# Cerebro_4_7.net
KiCad netlist of a schematic drawn in EAGLE
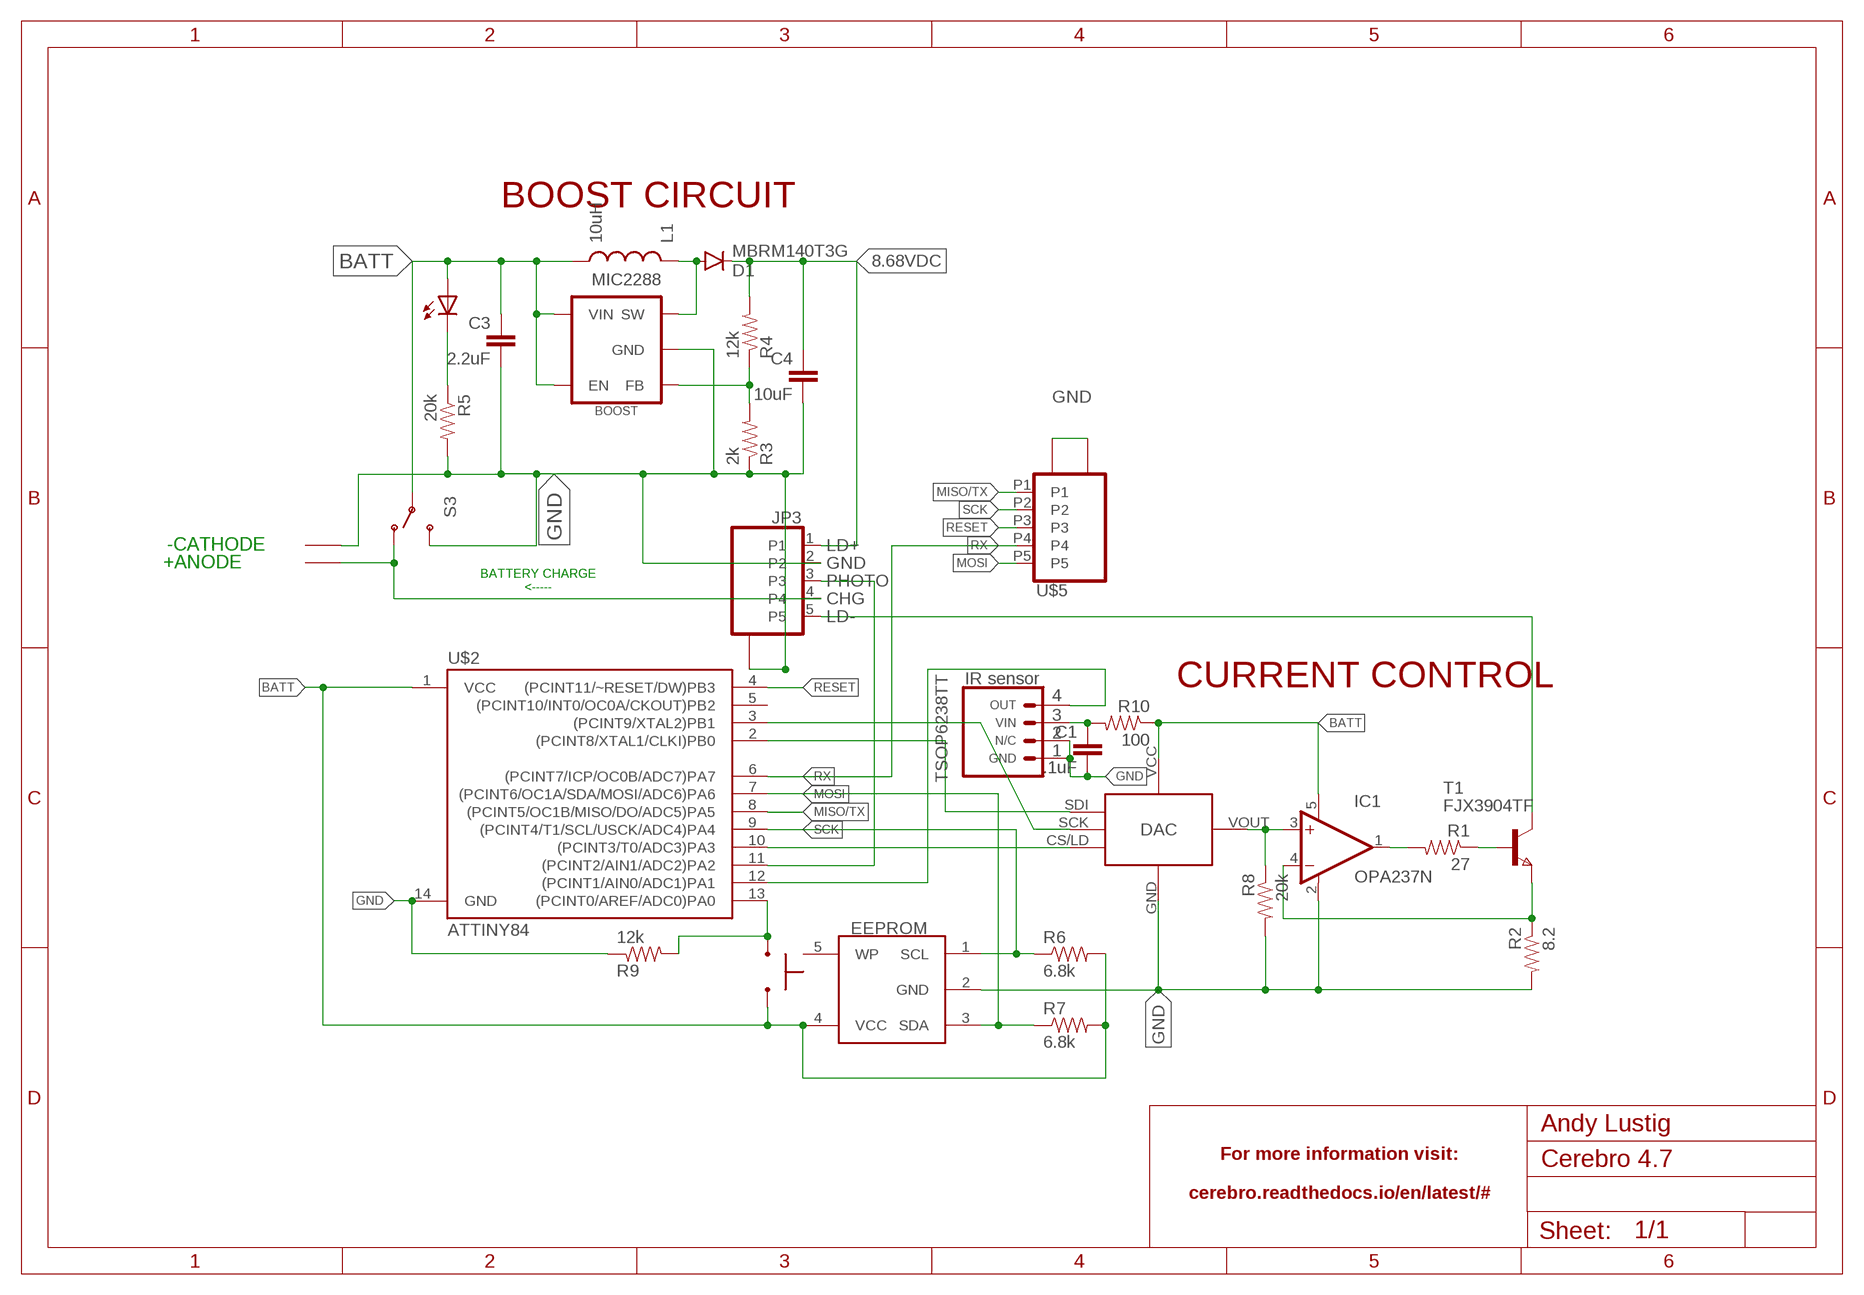
[diagram p0: schematic, sheet 1]

(export (version "E")
  (design (tool "Eeschema 10.0.6"))
  (components
    (comp (ref "C1")
      (value ".1uF")
      (footprint "eagle-import:0603-CAP")
      (libsource (lib "eagle-import") (part "CAP0603-CAP"))
    )
    (comp (ref "C3")
      (value "2.2uF")
      (footprint "eagle-import:0805")
      (libsource (lib "eagle-import") (part "CAP0805"))
    )
    (comp (ref "C4")
      (value "10uF")
      (footprint "eagle-import:0805")
      (libsource (lib "eagle-import") (part "CAP0805"))
    )
    (comp (ref "D1")
      (value "MBRM140T3G")
      (footprint "eagle-import:POWERMITE")
      (libsource (lib "eagle-import") (part "DIODEPOWERMITE"))
    )
    (comp (ref "IC1")
      (value "OPA237N")
      (footprint "eagle-import:SOT23-5")
      (fields (field (name "MF") "TEXAS INSTRUMENTS") (field (name "MPN") "OPA237NA/250"))
      (libsource (lib "eagle-import") (part "OPA237N"))
    )
    (comp (ref "INDICATOR_LED")
      (value "LED")
      (footprint "eagle-import:CHIP-LED0603")
      (libsource (lib "eagle-import") (part "LEDCHIP-LED0603"))
    )
    (comp (ref "JP3")
      (value "USB_MICROB_PLUG-PTH2")
      (footprint "eagle-import:MICRO-B-TH")
      (libsource (lib "eagle-import") (part "USB_MICROB_PLUG-PTH2"))
    )
    (comp (ref "L1")
      (value "10uH")
      (footprint "eagle-import:1812")
      (libsource (lib "eagle-import") (part "INDUCTORLQH4"))
    )
    (comp (ref "MIC2288")
      (value "BOOST")
      (footprint "eagle-import:SOT23-5")
      (libsource (lib "eagle-import") (part "BOOST_CONVERTER"))
    )
    (comp (ref "R1")
      (value "27")
      (footprint "eagle-import:0805")
      (libsource (lib "eagle-import") (part "RESISTOR0805-RES"))
    )
    (comp (ref "R2")
      (value "8.2")
      (footprint "eagle-import:0805")
      (libsource (lib "eagle-import") (part "RESISTOR0805-RES"))
    )
    (comp (ref "R3")
      (value "2k")
      (footprint "eagle-import:0805")
      (libsource (lib "eagle-import") (part "RESISTOR0805-RES"))
    )
    (comp (ref "R4")
      (value "12k")
      (footprint "eagle-import:0805")
      (libsource (lib "eagle-import") (part "RESISTOR0805-RES"))
    )
    (comp (ref "R5")
      (value "20k")
      (footprint "eagle-import:0603-RES")
      (libsource (lib "eagle-import") (part "RESISTOR0603-RES"))
    )
    (comp (ref "R6")
      (value "6.8k")
      (footprint "eagle-import:0805")
      (libsource (lib "eagle-import") (part "RESISTOR0805-RES"))
    )
    (comp (ref "R7")
      (value "6.8k")
      (footprint "eagle-import:0805")
      (libsource (lib "eagle-import") (part "RESISTOR0805-RES"))
    )
    (comp (ref "R8")
      (value "20k")
      (footprint "eagle-import:0805")
      (libsource (lib "eagle-import") (part "RESISTOR0805-RES"))
    )
    (comp (ref "R9")
      (value "12k")
      (footprint "eagle-import:0805")
      (libsource (lib "eagle-import") (part "RESISTOR0805-RES"))
    )
    (comp (ref "R10")
      (value "100")
      (footprint "eagle-import:0603-RES")
      (libsource (lib "eagle-import") (part "RESISTOR0603-RES"))
    )
    (comp (ref "S3")
      (value "SWITCH-SPDTSMD2")
      (footprint "eagle-import:SWITCH-SPDT-SMD")
      (libsource (lib "eagle-import") (part "SWITCH-SPDTSMD2"))
    )
    (comp (ref "SDF")
      (value "TSOP6238TT")
      (footprint "eagle-import:TSOP6")
      (libsource (lib "eagle-import") (part "TSOP6238TT"))
    )
    (comp (ref "T1")
      (value "FJX3904TF")
      (footprint "eagle-import:SOT323")
      (fields (field (name "MPN") "DSS4160U-7"))
      (libsource (lib "eagle-import") (part "NPNSOT323"))
    )
    (comp (ref "U$1")
      (value "DAC_LTC2630")
      (footprint "eagle-import:SC-70")
      (libsource (lib "eagle-import") (part "DAC_LTC2630"))
    )
    (comp (ref "U$2")
      (value "ATTINY84")
      (footprint "eagle-import:SO14")
      (libsource (lib "eagle-import") (part "ATTINY84"))
    )
    (comp (ref "U$3")
      (value "SWITCH-MOMENTARY-NO")
      (footprint "eagle-import:SWITCH_MOMENTARY_XS")
      (libsource (lib "eagle-import") (part "SWITCH-MOMENTARY-NO"))
    )
    (comp (ref "U$4")
      (value "EEPROM24C64A")
      (footprint "eagle-import:SOT23-5")
      (libsource (lib "eagle-import") (part "EEPROM24C64A"))
    )
    (comp (ref "U$5")
      (value "USB_SOCKET_MICRO_VERTHORIZONTAL")
      (footprint "eagle-import:USB_HORZ_MICRO_SMD")
      (libsource (lib "eagle-import") (part "USB_SOCKET_MICRO_VERTHORIZONTAL"))
    )
    (comp (ref "U$7")
      (value "BATT_TERMINAL")
      (footprint "eagle-import:BATT_TERMINAL")
      (libsource (lib "eagle-import") (part "BATT_TERMINAL"))
    )
    (comp (ref "U$8")
      (value "BATT_TERMINAL")
      (footprint "eagle-import:BATT_TERMINAL")
      (libsource (lib "eagle-import") (part "BATT_TERMINAL"))
    )
  )
  (nets
    (net (code "1") (name "8.68VDC") (class "Default")
      (node (ref "C4") (pin "1") (pinfunction "1_1") (pintype "passive"))
      (node (ref "D1") (pin "CATHODE") (pinfunction "C_CATHODE") (pintype "passive"))
      (node (ref "JP3") (pin "1") (pinfunction "P1_1") (pintype "bidirectional"))
      (node (ref "R4") (pin "2") (pinfunction "2_2") (pintype "passive"))
    )
    (net (code "2") (name "BATT") (class "Default")
      (node (ref "C3") (pin "1") (pinfunction "1_1") (pintype "passive"))
      (node (ref "IC1") (pin "5") (pinfunction "V+_5") (pintype "power_in"))
      (node (ref "INDICATOR_LED") (pin "A") (pinfunction "A_A") (pintype "passive"))
      (node (ref "L1") (pin "P$2") (pinfunction "2_P$2") (pintype "passive"))
      (node (ref "L1") (pin "P$4") (pinfunction "2_P$4") (pintype "passive"))
      (node (ref "MIC2288") (pin "4") (pinfunction "EN_4") (pintype "input"))
      (node (ref "MIC2288") (pin "5") (pinfunction "VIN_5") (pintype "passive"))
      (node (ref "R10") (pin "1") (pinfunction "1_1") (pintype "passive"))
      (node (ref "R6") (pin "2") (pinfunction "2_2") (pintype "passive"))
      (node (ref "R7") (pin "2") (pinfunction "2_2") (pintype "passive"))
      (node (ref "S3") (pin "2") (pinfunction "P_2") (pintype "passive"))
      (node (ref "U$1") (pin "VCC") (pinfunction "VIN_VCC") (pintype "bidirectional"))
      (node (ref "U$2") (pin "1") (pinfunction "VCC_1") (pintype "bidirectional"))
      (node (ref "U$3") (pin "P$2") (pinfunction "2_P$2") (pintype "bidirectional"))
      (node (ref "U$4") (pin "4") (pinfunction "VCC_4") (pintype "bidirectional"))
    )
    (net (code "3") (name "GND") (class "Default")
      (node (ref "C1") (pin "2") (pinfunction "2_2") (pintype "passive"))
      (node (ref "C3") (pin "2") (pinfunction "2_2") (pintype "passive"))
      (node (ref "C4") (pin "2") (pinfunction "2_2") (pintype "passive"))
      (node (ref "IC1") (pin "2") (pinfunction "V-_2") (pintype "power_in"))
      (node (ref "JP3") (pin "2") (pinfunction "P2_2") (pintype "bidirectional"))
      (node (ref "JP3") (pin "P$1") (pinfunction "P$1_P$1") (pintype "bidirectional"))
      (node (ref "JP3") (pin "P$2") (pinfunction "P$2_P$2") (pintype "bidirectional"))
      (node (ref "MIC2288") (pin "2") (pinfunction "GND_2") (pintype "input"))
      (node (ref "R2") (pin "2") (pinfunction "2_2") (pintype "passive"))
      (node (ref "R3") (pin "1") (pinfunction "1_1") (pintype "passive"))
      (node (ref "R5") (pin "2") (pinfunction "2_2") (pintype "passive"))
      (node (ref "R8") (pin "2") (pinfunction "2_2") (pintype "passive"))
      (node (ref "R9") (pin "1") (pinfunction "1_1") (pintype "passive"))
      (node (ref "S3") (pin "3") (pinfunction "S_3") (pintype "passive"))
      (node (ref "SDF") (pin "P$1") (pinfunction "1_P$1") (pintype "passive"))
      (node (ref "SDF") (pin "P$2") (pinfunction "2_P$2") (pintype "passive"))
      (node (ref "U$1") (pin "GND") (pinfunction "GND_GND") (pintype "bidirectional"))
      (node (ref "U$2") (pin "14") (pinfunction "GND_14") (pintype "bidirectional"))
      (node (ref "U$4") (pin "2") (pinfunction "GND_2") (pintype "bidirectional"))
      (node (ref "U$5") (pin "G1") (pinfunction "P$1_G1") (pintype "bidirectional"))
      (node (ref "U$5") (pin "G2") (pinfunction "P$2_G2") (pintype "bidirectional"))
      (node (ref "U$7") (pin "P$1") (pinfunction "P$1_P$1") (pintype "power_in"))
    )
    (net (code "4") (name "MISO{slash}TX") (class "Default")
      (node (ref "U$2") (pin "8") (pinfunction "(PCINT5/OC1B/MISO/DO/ADC5)PA5_8") (pintype "bidirectional"))
      (node (ref "U$5") (pin "P1") (pinfunction "P1_P1") (pintype "bidirectional"))
    )
    (net (code "5") (name "MOSI") (class "Default")
      (node (ref "R7") (pin "1") (pinfunction "1_1") (pintype "passive"))
      (node (ref "U$2") (pin "7") (pinfunction "(PCINT6/OC1A/SDA/MOSI/ADC6)PA6_7") (pintype "bidirectional"))
      (node (ref "U$4") (pin "3") (pinfunction "SDA_3") (pintype "bidirectional"))
      (node (ref "U$5") (pin "P5") (pinfunction "P5_P5") (pintype "bidirectional"))
    )
    (net (code "6") (name "Net-(D1-A)") (class "Default")
      (node (ref "D1") (pin "ANODE") (pinfunction "A_ANODE") (pintype "passive"))
      (node (ref "L1") (pin "P$1") (pinfunction "1_P$1") (pintype "passive"))
      (node (ref "L1") (pin "P$3") (pinfunction "1_P$3") (pintype "passive"))
      (node (ref "MIC2288") (pin "1") (pinfunction "SW_1") (pintype "input"))
    )
    (net (code "7") (name "Net-(IC1-+IN)") (class "Default")
      (node (ref "IC1") (pin "3") (pinfunction "+IN_3") (pintype "input"))
      (node (ref "R8") (pin "1") (pinfunction "1_1") (pintype "passive"))
      (node (ref "U$1") (pin "VOUT") (pinfunction "VOUT_VOUT") (pintype "bidirectional"))
    )
    (net (code "8") (name "Net-(IC1--IN)") (class "Default")
      (node (ref "IC1") (pin "4") (pinfunction "-IN_4") (pintype "input"))
      (node (ref "R2") (pin "1") (pinfunction "1_1") (pintype "passive"))
      (node (ref "T1") (pin "3") (pinfunction "E_3") (pintype "passive"))
    )
    (net (code "9") (name "Net-(IC1-OUT)") (class "Default")
      (node (ref "IC1") (pin "1") (pinfunction "OUT_1") (pintype "output"))
      (node (ref "R1") (pin "2") (pinfunction "2_2") (pintype "passive"))
    )
    (net (code "10") (name "Net-(INDICATOR_LED-PadC)") (class "Default")
      (node (ref "INDICATOR_LED") (pin "C") (pinfunction "C_C") (pintype "passive"))
      (node (ref "R5") (pin "1") (pinfunction "1_1") (pintype "passive"))
    )
    (net (code "11") (name "Net-(JP3-P3)") (class "Default")
      (node (ref "JP3") (pin "3") (pinfunction "P3_3") (pintype "bidirectional"))
      (node (ref "U$2") (pin "11") (pinfunction "(PCINT2/AIN1/ADC2)PA2_11") (pintype "bidirectional"))
    )
    (net (code "12") (name "Net-(JP3-P4)") (class "Default")
      (node (ref "JP3") (pin "4") (pinfunction "P4_4") (pintype "bidirectional"))
      (node (ref "S3") (pin "1") (pinfunction "O_1") (pintype "passive"))
      (node (ref "U$8") (pin "P$1") (pinfunction "P$1_P$1") (pintype "power_in"))
    )
    (net (code "13") (name "Net-(JP3-P5)") (class "Default")
      (node (ref "JP3") (pin "5") (pinfunction "P5_5") (pintype "bidirectional"))
      (node (ref "T1") (pin "1") (pinfunction "C_1") (pintype "passive"))
    )
    (net (code "14") (name "Net-(MIC2288-FB)") (class "Default")
      (node (ref "MIC2288") (pin "3") (pinfunction "FB_3") (pintype "input"))
      (node (ref "R3") (pin "2") (pinfunction "2_2") (pintype "passive"))
      (node (ref "R4") (pin "1") (pinfunction "1_1") (pintype "passive"))
    )
    (net (code "15") (name "Net-(SDF-3)") (class "Default")
      (node (ref "C1") (pin "1") (pinfunction "1_1") (pintype "passive"))
      (node (ref "R10") (pin "2") (pinfunction "2_2") (pintype "passive"))
      (node (ref "SDF") (pin "P$3") (pinfunction "3_P$3") (pintype "passive"))
    )
    (net (code "16") (name "Net-(SDF-4)") (class "Default")
      (node (ref "SDF") (pin "P$4") (pinfunction "4_P$4") (pintype "passive"))
      (node (ref "U$2") (pin "12") (pinfunction "(PCINT1/AIN0/ADC1)PA1_12") (pintype "bidirectional"))
    )
    (net (code "17") (name "Net-(T1-B)") (class "Default")
      (node (ref "R1") (pin "1") (pinfunction "1_1") (pintype "passive"))
      (node (ref "T1") (pin "2") (pinfunction "B_2") (pintype "passive"))
    )
    (net (code "18") (name "Net-(U$2-(PCINT0{slash}AREF{slash}ADC0)PA0)") (class "Default")
      (node (ref "R9") (pin "2") (pinfunction "2_2") (pintype "passive"))
      (node (ref "U$2") (pin "13") (pinfunction "(PCINT0/AREF/ADC0)PA0_13") (pintype "bidirectional"))
      (node (ref "U$3") (pin "P$1") (pinfunction "1_P$1") (pintype "bidirectional"))
    )
    (net (code "19") (name "Net-(U$2-(PCINT3{slash}T0{slash}ADC3)PA3)") (class "Default")
      (node (ref "U$1") (pin "CS/LD") (pinfunction "CS/LD_CS/LD") (pintype "bidirectional"))
      (node (ref "U$2") (pin "10") (pinfunction "(PCINT3/T0/ADC3)PA3_10") (pintype "bidirectional"))
    )
    (net (code "20") (name "Net-(U$2-(PCINT8{slash}XTAL1{slash}CLKI)PB0)") (class "Default")
      (node (ref "U$1") (pin "SDI") (pinfunction "SDI_SDI") (pintype "bidirectional"))
      (node (ref "U$2") (pin "2") (pinfunction "(PCINT8/XTAL1/CLKI)PB0_2") (pintype "bidirectional"))
    )
    (net (code "21") (name "Net-(U$2-(PCINT9{slash}XTAL2)PB1)") (class "Default")
      (node (ref "U$1") (pin "SCK") (pinfunction "SCK_SCK") (pintype "bidirectional"))
      (node (ref "U$2") (pin "3") (pinfunction "(PCINT9/XTAL2)PB1_3") (pintype "bidirectional"))
    )
    (net (code "22") (name "RESET") (class "Default")
      (node (ref "U$2") (pin "4") (pinfunction "(PCINT11/~{RESET/DW})PB3_4") (pintype "bidirectional"))
      (node (ref "U$5") (pin "P3") (pinfunction "P3_P3") (pintype "bidirectional"))
    )
    (net (code "23") (name "RX") (class "Default")
      (node (ref "U$2") (pin "6") (pinfunction "(PCINT7/ICP/OC0B/ADC7)PA7_6") (pintype "bidirectional"))
      (node (ref "U$5") (pin "P4") (pinfunction "P4_P4") (pintype "bidirectional"))
    )
    (net (code "24") (name "SCK") (class "Default")
      (node (ref "R6") (pin "1") (pinfunction "1_1") (pintype "passive"))
      (node (ref "U$2") (pin "9") (pinfunction "(PCINT4/T1/SCL/USCK/ADC4)PA4_9") (pintype "bidirectional"))
      (node (ref "U$4") (pin "1") (pinfunction "SCL_1") (pintype "bidirectional"))
      (node (ref "U$5") (pin "P2") (pinfunction "P2_P2") (pintype "bidirectional"))
    )
    (net (code "25") (name "unconnected-(U$2-(PCINT10{slash}INT0{slash}OC0A{slash}CKOUT)PB2-Pad5)") (class "Default")
      (node (ref "U$2") (pin "5") (pinfunction "(PCINT10/INT0/OC0A/CKOUT)PB2_5") (pintype "bidirectional"))
    )
    (net (code "26") (name "unconnected-(U$4-WP-Pad5)") (class "Default")
      (node (ref "U$4") (pin "5") (pinfunction "WP_5") (pintype "bidirectional"))
    )
  )
)
